# 10_Speaker_Microphone.net
KiCad netlist of a schematic drawn in Altium Designer
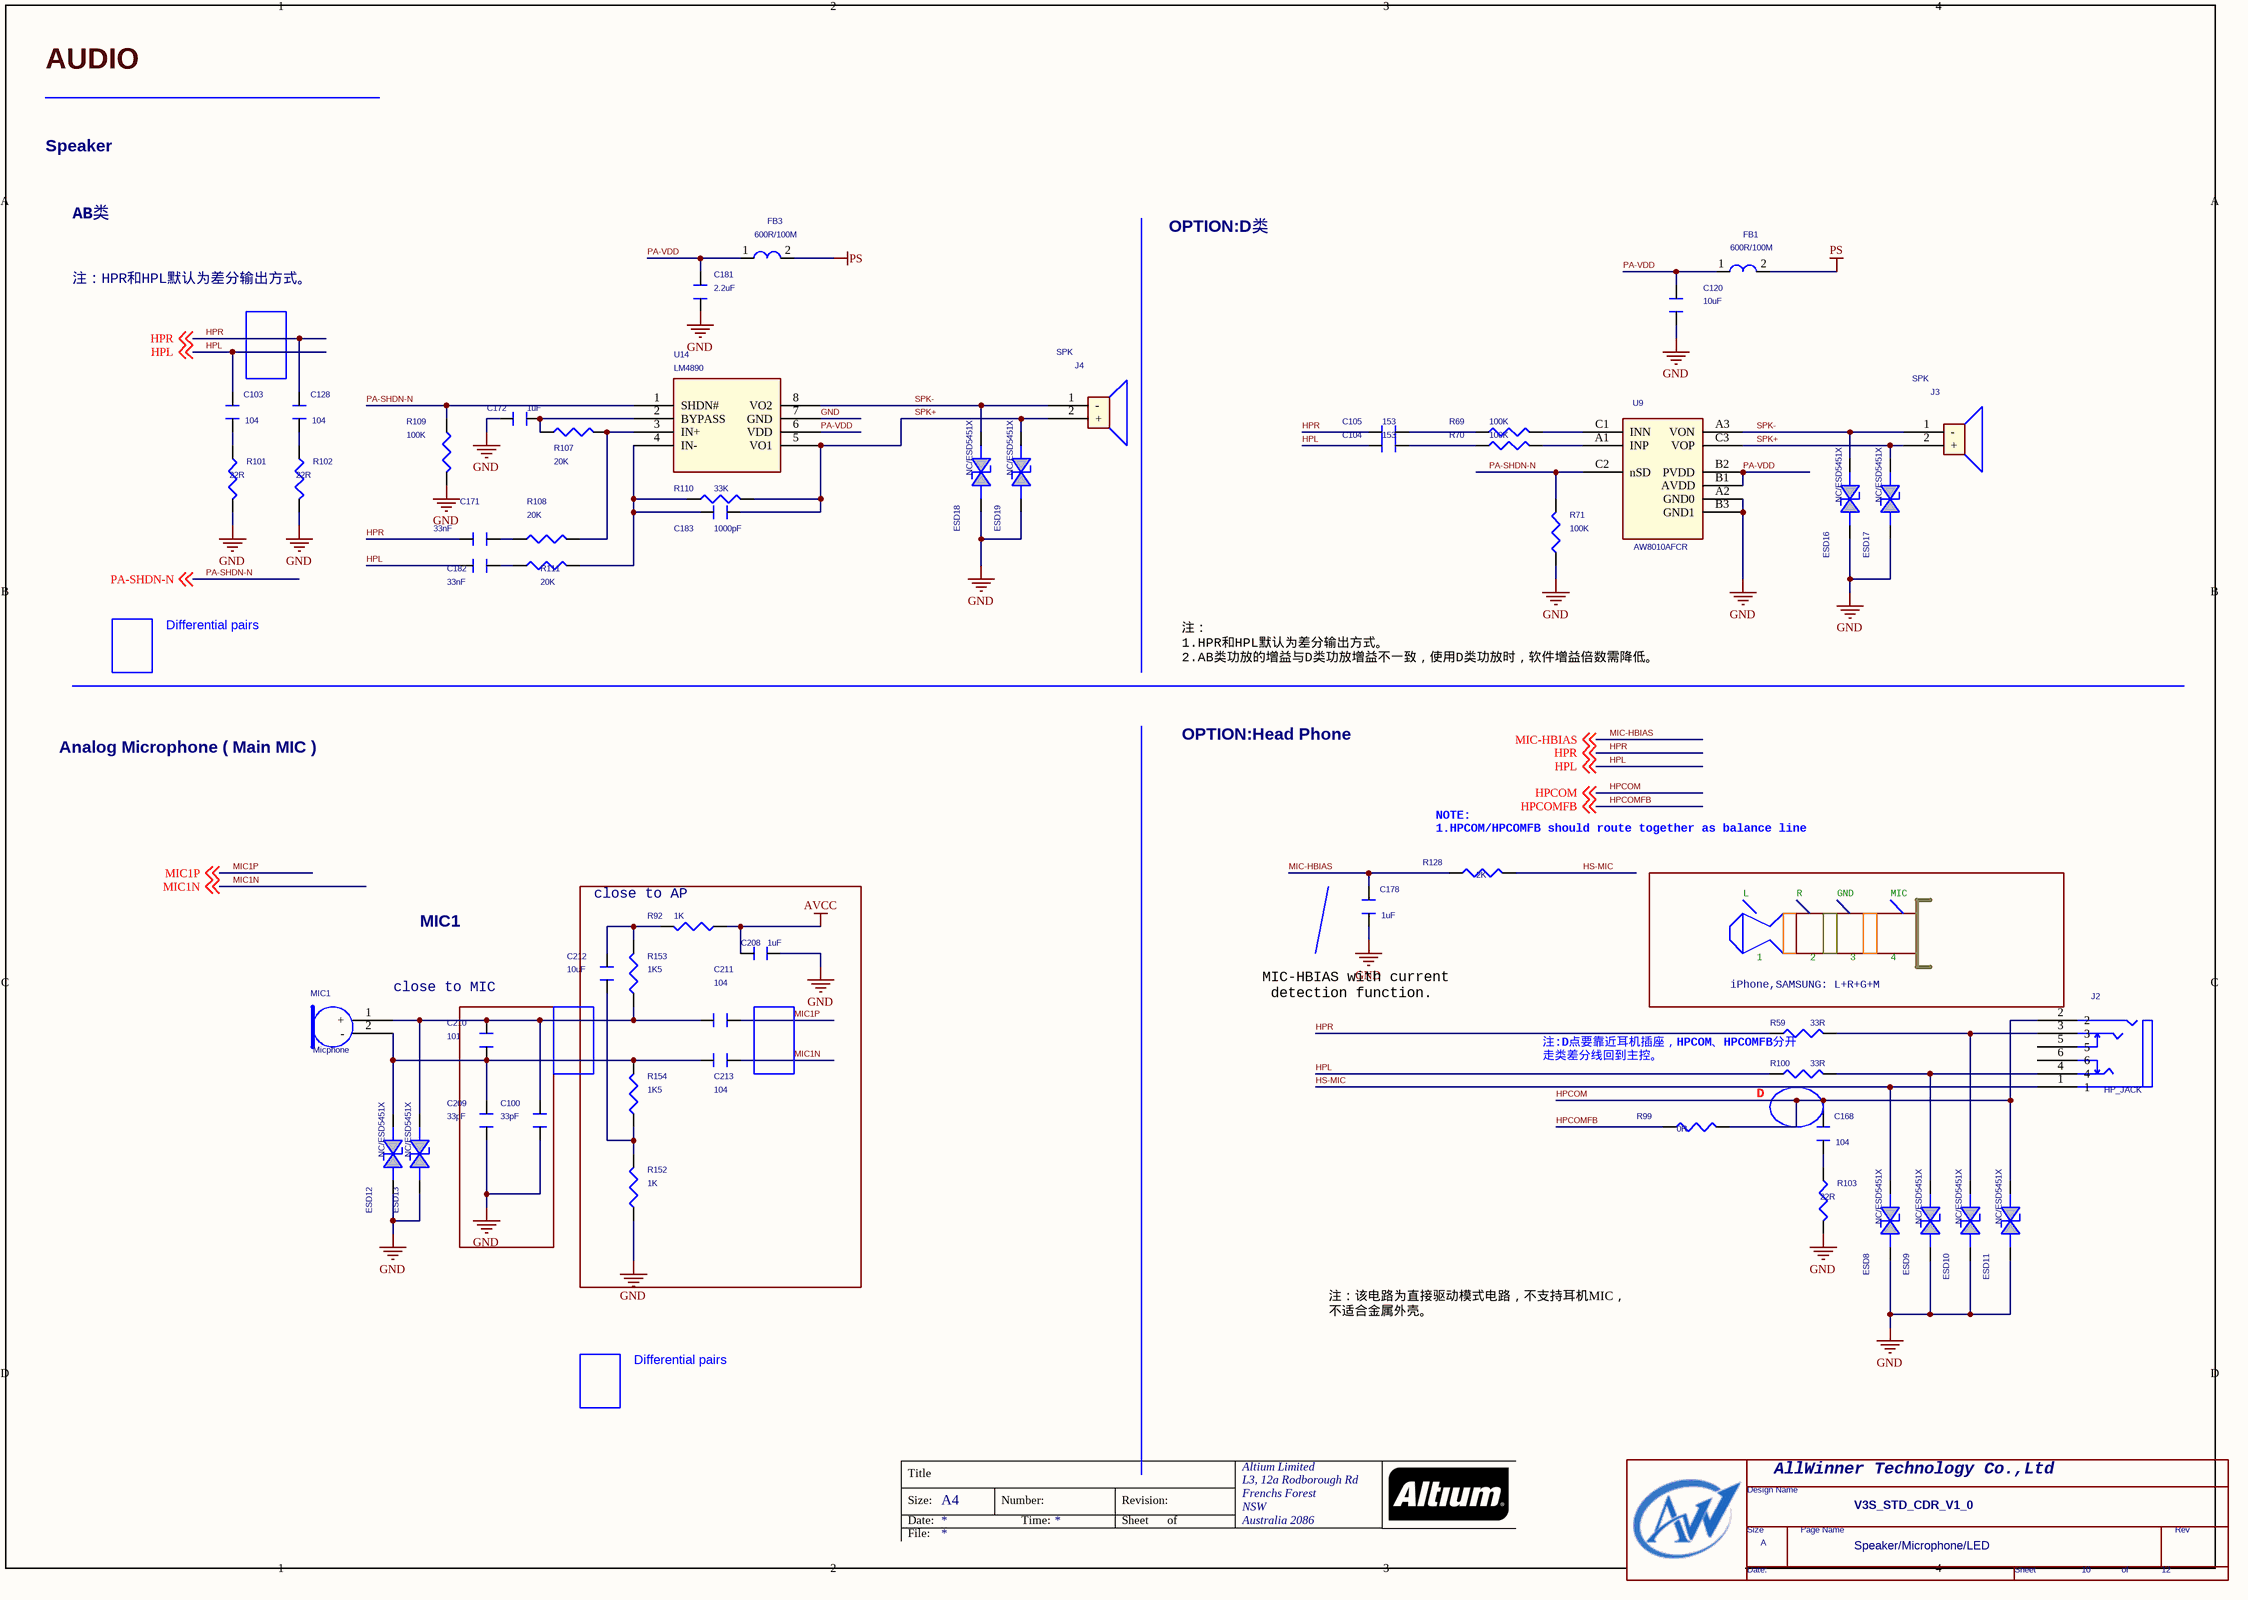
[diagram p0: 10 Speaker_Microphone.SchDoc]

(export (version "E")
  (design (tool "Eeschema 10.0.6"))
  (components
    (comp (ref "C100") (value "33pF") (footprint "C0402") (libsource (lib "*") (part "CAPACITOR")))
    (comp (ref "C103") (value "104") (footprint "C0402") (libsource (lib "*") (part "CAPACITOR_Dup1")))
    (comp (ref "C104") (value "153") (footprint "C0402") (libsource (lib "*") (part "CAPACITOR_0_Dup5")))
    (comp (ref "C105") (value "153") (footprint "C0402") (libsource (lib "*") (part "CAPACITOR_0_Dup5")))
    (comp (ref "C120") (value "10uF") (footprint "C0603") (libsource (lib "*") (part "CAPACITOR_Dup1")))
    (comp (ref "C128") (value "104") (footprint "C0402") (libsource (lib "*") (part "CAPACITOR_Dup1")))
    (comp (ref "C168") (value "104") (footprint "C0402") (libsource (lib "*") (part "CAPACITOR_Dup1")))
    (comp (ref "C171") (value "33nF") (footprint "C0402") (libsource (lib "*") (part "CAPACITOR_0_Dup3")))
    (comp (ref "C172") (value "1uF") (footprint "C0402") (libsource (lib "*") (part "CAPACITOR_0_Dup3")))
    (comp (ref "C178") (value "1uF") (footprint "C0402") (libsource (lib "*") (part "CAPACITOR_Dup1")))
    (comp (ref "C181") (value "2.2uF") (footprint "C0402") (libsource (lib "*") (part "CAPACITOR_0_Dup3")))
    (comp (ref "C182") (value "33nF") (footprint "C0402") (libsource (lib "*") (part "CAPACITOR_0_Dup3")))
    (comp (ref "C183") (value "1000pF") (footprint "C0402") (libsource (lib "*") (part "CAPACITOR_0_Dup3")))
    (comp (ref "C208") (value "1uF") (footprint "C0402") (libsource (lib "*") (part "CAPACITOR")))
    (comp (ref "C209") (value "33pF") (footprint "C0402") (libsource (lib "*") (part "CAPACITOR")))
    (comp (ref "C210") (value "101") (footprint "C0402") (libsource (lib "*") (part "CAPACITOR")))
    (comp (ref "C211") (value "104") (footprint "C0402") (libsource (lib "*") (part "CAPACITOR_Dup1")))
    (comp (ref "C212") (value "10uF") (footprint "C0603") (libsource (lib "*") (part "CAPACITOR_Dup1")))
    (comp (ref "C213") (value "104") (footprint "C0402") (libsource (lib "*") (part "CAPACITOR_Dup1")))
    (comp (ref "ESD8") (value "NC/ESD5451X") (footprint "ESD0402") (libsource (lib "*") (part "1_1.5KE100A")))
    (comp (ref "ESD9") (value "NC/ESD5451X") (footprint "ESD0402") (libsource (lib "*") (part "1_1.5KE100A")))
    (comp (ref "ESD10")
      (value "NC/ESD5451X")
      (footprint "ESD0402")
      (libsource (lib "*") (part "1_1.5KE100A"))
    )
    (comp (ref "ESD11")
      (value "NC/ESD5451X")
      (footprint "ESD0402")
      (libsource (lib "*") (part "1_1.5KE100A"))
    )
    (comp (ref "ESD12")
      (value "NC/ESD5451X")
      (footprint "ESD0402")
      (libsource (lib "*") (part "1_1.5KE100A"))
    )
    (comp (ref "ESD13")
      (value "NC/ESD5451X")
      (footprint "ESD0402")
      (libsource (lib "*") (part "1_1.5KE100A"))
    )
    (comp (ref "ESD16")
      (value "NC/ESD5451X")
      (footprint "ESD0402")
      (libsource (lib "*") (part "1_1.5KE100A"))
    )
    (comp (ref "ESD17")
      (value "NC/ESD5451X")
      (footprint "ESD0402")
      (libsource (lib "*") (part "1_1.5KE100A"))
    )
    (comp (ref "ESD18")
      (value "NC/ESD5451X")
      (footprint "ESD0402")
      (libsource (lib "*") (part "1_1.5KE100A"))
    )
    (comp (ref "ESD19")
      (value "NC/ESD5451X")
      (footprint "ESD0402")
      (libsource (lib "*") (part "1_1.5KE100A"))
    )
    (comp (ref "FB1")
      (value "600R/100M")
      (footprint "L0603")
      (description "RoHS BEAD/600ohm 100Mhz Z=600Ω DCR<0.2Ω 800mA SMT L0603")
      (libsource (lib "*") (part "INDUCTOR_0_Dup1"))
    )
    (comp (ref "FB3")
      (value "600R/100M")
      (footprint "L0603")
      (description "RoHS BEAD/600ohm 100Mhz Z=600Ω DCR<0.2Ω 800mA SMT L0603")
      (libsource (lib "*") (part "INDUCTOR_0_Dup1"))
    )
    (comp (ref "J2") (value "HP_JACK") (footprint "EAR-JACK-3-5") (libsource (lib "*") (part "USB_WIFI_0")))
    (comp (ref "J3") (value "SPK") (footprint "Phone Connector") (libsource (lib "*") (part "SPEAKER")))
    (comp (ref "J4") (value "SPK") (footprint "Phone Connector") (libsource (lib "*") (part "SPEAKER")))
    (comp (ref "MIC1")
      (value "Micphone")
      (footprint "Micphone Connector")
      (libsource (lib "*") (part "Micphone_0"))
    )
    (comp (ref "R59") (value "33R") (footprint "R0805") (libsource (lib "*") (part "R_Dup3")))
    (comp (ref "R69") (value "100K") (footprint "R0402") (libsource (lib "*") (part "RESISTOR_Dup2")))
    (comp (ref "R70") (value "100K") (footprint "R0402") (libsource (lib "*") (part "RESISTOR_Dup2")))
    (comp (ref "R71") (value "100K") (footprint "R0402") (libsource (lib "*") (part "R_Dup1")))
    (comp (ref "R92") (value "1K") (footprint "R0402") (libsource (lib "*") (part "R_Dup4")))
    (comp (ref "R99") (value "0R") (footprint "0805") (libsource (lib "*") (part "R1 0805_Dup1")))
    (comp (ref "R100") (value "33R") (footprint "R0805") (libsource (lib "*") (part "R_Dup3")))
    (comp (ref "R101") (value "22R") (footprint "0805") (libsource (lib "*") (part "R1 0805_Dup1")))
    (comp (ref "R102") (value "22R") (footprint "0805") (libsource (lib "*") (part "R1 0805_Dup1")))
    (comp (ref "R103") (value "22R") (footprint "0805") (libsource (lib "*") (part "R1 0805_Dup1")))
    (comp (ref "R107") (value "20K") (footprint "R0402") (libsource (lib "*") (part "?_0")))
    (comp (ref "R108") (value "20K") (footprint "R0402") (libsource (lib "*") (part "?_0")))
    (comp (ref "R109") (value "100K") (footprint "R0402") (libsource (lib "*") (part "?_0")))
    (comp (ref "R110") (value "33K") (footprint "R0402") (libsource (lib "*") (part "?_0")))
    (comp (ref "R111") (value "20K") (footprint "R0402") (libsource (lib "*") (part "?_0")))
    (comp (ref "R128") (value "2K") (footprint "R0402") (libsource (lib "*") (part "R_Dup4")))
    (comp (ref "R152") (value "1K") (footprint "R0402") (libsource (lib "*") (part "R_Dup4")))
    (comp (ref "R153") (value "1K5") (footprint "R0402") (libsource (lib "*") (part "R_Dup4")))
    (comp (ref "R154") (value "1K5") (footprint "R0402") (libsource (lib "*") (part "R_Dup4")))
    (comp (ref "U9") (value "AW8010AFCR") (footprint "CSP9") (libsource (lib "*") (part "AW8010CSR_1")))
    (comp (ref "U14") (value "LM4890") (footprint "MSOP8") (libsource (lib "*") (part "LY8006_0")))
  )
  (nets
    (net (code "1") (name "/HS-MIC") (class "Default")
      (node (ref "ESD8") (pin "1") (pinfunction "ANODE_1") (pintype "passive"))
      (node (ref "J2") (pin "1") (pinfunction "1_1") (pintype "passive"))
      (node (ref "R128") (pin "1") (pinfunction "1_1") (pintype "passive"))
    )
    (net (code "2") (name "/PA-VDD") (class "Default")
      (node (ref "C120") (pin "2") (pinfunction "2_2") (pintype "passive"))
      (node (ref "C181") (pin "2") (pinfunction "2_2") (pintype "passive"))
      (node (ref "FB1") (pin "1") (pinfunction "1_1") (pintype "passive"))
      (node (ref "FB3") (pin "1") (pinfunction "1_1") (pintype "passive"))
      (node (ref "U14") (pin "6") (pinfunction "VDD_6") (pintype "passive"))
      (node (ref "U9") (pin "B1") (pinfunction "AVDD_B1") (pintype "passive"))
      (node (ref "U9") (pin "B2") (pinfunction "PVDD_B2") (pintype "passive"))
    )
    (net (code "3") (name "/SPK+") (class "Default")
      (node (ref "C183") (pin "2") (pinfunction "2_2") (pintype "passive"))
      (node (ref "ESD17") (pin "1") (pinfunction "ANODE_1") (pintype "passive"))
      (node (ref "ESD19") (pin "1") (pinfunction "ANODE_1") (pintype "passive"))
      (node (ref "J3") (pin "2") (pinfunction "+_2") (pintype "passive"))
      (node (ref "J4") (pin "2") (pinfunction "+_2") (pintype "passive"))
      (node (ref "R110") (pin "2") (pinfunction "2_2") (pintype "passive"))
      (node (ref "U14") (pin "5") (pinfunction "VO1_5") (pintype "passive"))
      (node (ref "U9") (pin "C3") (pinfunction "VOP_C3") (pintype "passive"))
    )
    (net (code "4") (name "/SPK-") (class "Default")
      (node (ref "ESD16") (pin "1") (pinfunction "ANODE_1") (pintype "passive"))
      (node (ref "ESD18") (pin "1") (pinfunction "ANODE_1") (pintype "passive"))
      (node (ref "J3") (pin "1") (pinfunction "-_1") (pintype "passive"))
      (node (ref "J4") (pin "1") (pinfunction "-_1") (pintype "passive"))
      (node (ref "U14") (pin "8") (pinfunction "VO2_8") (pintype "passive"))
      (node (ref "U9") (pin "A3") (pinfunction "VON_A3") (pintype "passive"))
    )
    (net (code "5") (name "AVCC") (class "Default")
      (node (ref "C208") (pin "2") (pinfunction "2_2") (pintype "passive"))
      (node (ref "R92") (pin "1") (pinfunction "1_1") (pintype "passive"))
    )
    (net (code "6") (name "GND") (class "Default")
      (node (ref "C100") (pin "1") (pinfunction "1_1") (pintype "passive"))
      (node (ref "C120") (pin "1") (pinfunction "1_1") (pintype "passive"))
      (node (ref "C172") (pin "1") (pinfunction "1_1") (pintype "passive"))
      (node (ref "C178") (pin "1") (pinfunction "1_1") (pintype "passive"))
      (node (ref "C181") (pin "1") (pinfunction "1_1") (pintype "passive"))
      (node (ref "C208") (pin "1") (pinfunction "1_1") (pintype "passive"))
      (node (ref "C209") (pin "1") (pinfunction "1_1") (pintype "passive"))
      (node (ref "ESD10") (pin "2") (pinfunction "CATHODE_2") (pintype "passive"))
      (node (ref "ESD11") (pin "2") (pinfunction "CATHODE_2") (pintype "passive"))
      (node (ref "ESD12") (pin "2") (pinfunction "CATHODE_2") (pintype "passive"))
      (node (ref "ESD13") (pin "2") (pinfunction "CATHODE_2") (pintype "passive"))
      (node (ref "ESD16") (pin "2") (pinfunction "CATHODE_2") (pintype "passive"))
      (node (ref "ESD17") (pin "2") (pinfunction "CATHODE_2") (pintype "passive"))
      (node (ref "ESD18") (pin "2") (pinfunction "CATHODE_2") (pintype "passive"))
      (node (ref "ESD19") (pin "2") (pinfunction "CATHODE_2") (pintype "passive"))
      (node (ref "ESD8") (pin "2") (pinfunction "CATHODE_2") (pintype "passive"))
      (node (ref "ESD9") (pin "2") (pinfunction "CATHODE_2") (pintype "passive"))
      (node (ref "R101") (pin "1") (pinfunction "1_1") (pintype "passive"))
      (node (ref "R102") (pin "1") (pinfunction "1_1") (pintype "passive"))
      (node (ref "R103") (pin "1") (pinfunction "1_1") (pintype "passive"))
      (node (ref "R109") (pin "2") (pinfunction "2_2") (pintype "passive"))
      (node (ref "R152") (pin "1") (pinfunction "1_1") (pintype "passive"))
      (node (ref "R71") (pin "1") (pinfunction "1_1") (pintype "passive"))
      (node (ref "U14") (pin "7") (pinfunction "GND_7") (pintype "passive"))
      (node (ref "U9") (pin "A2") (pinfunction "GND0_A2") (pintype "passive"))
      (node (ref "U9") (pin "B3") (pinfunction "GND1_B3") (pintype "passive"))
    )
    (net (code "7") (name "HPCOM") (class "Default")
      (node (ref "C168") (pin "2") (pinfunction "2_2") (pintype "passive"))
      (node (ref "ESD11") (pin "1") (pinfunction "ANODE_1") (pintype "passive"))
      (node (ref "J2") (pin "2") (pinfunction "2_2") (pintype "passive"))
      (node (ref "R99") (pin "1") (pinfunction "1_1") (pintype "passive"))
    )
    (net (code "8") (name "HPCOMFB") (class "Default")
      (node (ref "R99") (pin "2") (pinfunction "2_2") (pintype "passive"))
    )
    (net (code "9") (name "HPL") (class "Default")
      (node (ref "C103") (pin "2") (pinfunction "2_2") (pintype "passive"))
      (node (ref "C104") (pin "2") (pinfunction "2_2") (pintype "passive"))
      (node (ref "C182") (pin "1") (pinfunction "1_1") (pintype "passive"))
      (node (ref "R100") (pin "1") (pinfunction "1_1") (pintype "passive"))
    )
    (net (code "10") (name "HPR") (class "Default")
      (node (ref "C105") (pin "2") (pinfunction "2_2") (pintype "passive"))
      (node (ref "C128") (pin "2") (pinfunction "2_2") (pintype "passive"))
      (node (ref "C171") (pin "1") (pinfunction "1_1") (pintype "passive"))
      (node (ref "R59") (pin "1") (pinfunction "1_1") (pintype "passive"))
    )
    (net (code "11") (name "MIC-HBIAS") (class "Default")
      (node (ref "C178") (pin "2") (pinfunction "2_2") (pintype "passive"))
      (node (ref "R128") (pin "2") (pinfunction "2_2") (pintype "passive"))
    )
    (net (code "12") (name "MIC1N") (class "Default")
      (node (ref "C213") (pin "1") (pinfunction "1_1") (pintype "passive"))
    )
    (net (code "13") (name "MIC1P") (class "Default")
      (node (ref "C211") (pin "1") (pinfunction "1_1") (pintype "passive"))
    )
    (net (code "14") (name "Net-(C103-Pad1)") (class "Default")
      (node (ref "C103") (pin "1") (pinfunction "1_1") (pintype "passive"))
      (node (ref "R101") (pin "2") (pinfunction "2_2") (pintype "passive"))
    )
    (net (code "15") (name "Net-(C104-Pad1)") (class "Default")
      (node (ref "C104") (pin "1") (pinfunction "1_1") (pintype "passive"))
      (node (ref "R70") (pin "1") (pinfunction "1_1") (pintype "passive"))
    )
    (net (code "16") (name "Net-(C105-Pad1)") (class "Default")
      (node (ref "C105") (pin "1") (pinfunction "1_1") (pintype "passive"))
      (node (ref "R69") (pin "1") (pinfunction "1_1") (pintype "passive"))
    )
    (net (code "17") (name "Net-(C128-Pad1)") (class "Default")
      (node (ref "C128") (pin "1") (pinfunction "1_1") (pintype "passive"))
      (node (ref "R102") (pin "2") (pinfunction "2_2") (pintype "passive"))
    )
    (net (code "18") (name "Net-(C168-Pad1)") (class "Default")
      (node (ref "C168") (pin "1") (pinfunction "1_1") (pintype "passive"))
      (node (ref "R103") (pin "2") (pinfunction "2_2") (pintype "passive"))
    )
    (net (code "19") (name "Net-(C171-Pad2)") (class "Default")
      (node (ref "C171") (pin "2") (pinfunction "2_2") (pintype "passive"))
      (node (ref "R108") (pin "1") (pinfunction "1_1") (pintype "passive"))
    )
    (net (code "20") (name "Net-(C182-Pad2)") (class "Default")
      (node (ref "C182") (pin "2") (pinfunction "2_2") (pintype "passive"))
      (node (ref "R111") (pin "1") (pinfunction "1_1") (pintype "passive"))
    )
    (net (code "21") (name "Net-(C212-Pad1)") (class "Default")
      (node (ref "C212") (pin "1") (pinfunction "1_1") (pintype "passive"))
      (node (ref "R152") (pin "2") (pinfunction "2_2") (pintype "passive"))
      (node (ref "R154") (pin "1") (pinfunction "1_1") (pintype "passive"))
    )
    (net (code "22") (name "Net-(C212-Pad2)") (class "Default")
      (node (ref "C212") (pin "2") (pinfunction "2_2") (pintype "passive"))
      (node (ref "R153") (pin "2") (pinfunction "2_2") (pintype "passive"))
      (node (ref "R92") (pin "2") (pinfunction "2_2") (pintype "passive"))
    )
    (net (code "23") (name "Net-(ESD9-ANODE)") (class "Default")
      (node (ref "ESD9") (pin "1") (pinfunction "ANODE_1") (pintype "passive"))
      (node (ref "J2") (pin "4") (pinfunction "4_4") (pintype "passive"))
      (node (ref "R100") (pin "2") (pinfunction "2_2") (pintype "passive"))
    )
    (net (code "24") (name "Net-(ESD10-ANODE)") (class "Default")
      (node (ref "ESD10") (pin "1") (pinfunction "ANODE_1") (pintype "passive"))
      (node (ref "J2") (pin "3") (pinfunction "3_3") (pintype "passive"))
      (node (ref "R59") (pin "2") (pinfunction "2_2") (pintype "passive"))
    )
    (net (code "25") (name "Net-(ESD12-ANODE)") (class "Default")
      (node (ref "C209") (pin "2") (pinfunction "2_2") (pintype "passive"))
      (node (ref "C210") (pin "1") (pinfunction "1_1") (pintype "passive"))
      (node (ref "C213") (pin "2") (pinfunction "2_2") (pintype "passive"))
      (node (ref "ESD12") (pin "1") (pinfunction "ANODE_1") (pintype "passive"))
      (node (ref "MIC1") (pin "2") (pinfunction "-_2") (pintype "passive"))
      (node (ref "R154") (pin "2") (pinfunction "2_2") (pintype "passive"))
    )
    (net (code "26") (name "Net-(ESD13-ANODE)") (class "Default")
      (node (ref "C100") (pin "2") (pinfunction "2_2") (pintype "passive"))
      (node (ref "C210") (pin "2") (pinfunction "2_2") (pintype "passive"))
      (node (ref "C211") (pin "2") (pinfunction "2_2") (pintype "passive"))
      (node (ref "ESD13") (pin "1") (pinfunction "ANODE_1") (pintype "passive"))
      (node (ref "MIC1") (pin "1") (pinfunction "+_1") (pintype "passive"))
      (node (ref "R153") (pin "1") (pinfunction "1_1") (pintype "passive"))
    )
    (net (code "27") (name "Net-(U9-INN)") (class "Default")
      (node (ref "R69") (pin "2") (pinfunction "2_2") (pintype "passive"))
      (node (ref "U9") (pin "C1") (pinfunction "INN_C1") (pintype "passive"))
    )
    (net (code "28") (name "Net-(U9-INP)") (class "Default")
      (node (ref "R70") (pin "2") (pinfunction "2_2") (pintype "passive"))
      (node (ref "U9") (pin "A1") (pinfunction "INP_A1") (pintype "passive"))
    )
    (net (code "29") (name "Net-(U14-BYPASS)") (class "Default")
      (node (ref "C172") (pin "2") (pinfunction "2_2") (pintype "passive"))
      (node (ref "R107") (pin "1") (pinfunction "1_1") (pintype "passive"))
      (node (ref "U14") (pin "2") (pinfunction "BYPASS_2") (pintype "passive"))
    )
    (net (code "30") (name "Net-(U14-IN+)") (class "Default")
      (node (ref "R107") (pin "2") (pinfunction "2_2") (pintype "passive"))
      (node (ref "R108") (pin "2") (pinfunction "2_2") (pintype "passive"))
      (node (ref "U14") (pin "3") (pinfunction "IN+_3") (pintype "passive"))
    )
    (net (code "31") (name "Net-(U14-IN-)") (class "Default")
      (node (ref "C183") (pin "1") (pinfunction "1_1") (pintype "passive"))
      (node (ref "R110") (pin "1") (pinfunction "1_1") (pintype "passive"))
      (node (ref "R111") (pin "2") (pinfunction "2_2") (pintype "passive"))
      (node (ref "U14") (pin "4") (pinfunction "IN-_4") (pintype "passive"))
    )
    (net (code "32") (name "PA-SHDN-N") (class "Default")
      (node (ref "R109") (pin "1") (pinfunction "1_1") (pintype "passive"))
      (node (ref "R71") (pin "2") (pinfunction "2_2") (pintype "passive"))
      (node (ref "U14") (pin "1") (pinfunction "SHDN#_1") (pintype "passive"))
      (node (ref "U9") (pin "C2") (pinfunction "nSD_C2") (pintype "passive"))
    )
    (net (code "33") (name "PS") (class "Default")
      (node (ref "FB1") (pin "2") (pinfunction "2_2") (pintype "passive"))
      (node (ref "FB3") (pin "2") (pinfunction "2_2") (pintype "passive"))
    )
    (net (code "34") (name "unconnected-(J2-Pad5)") (class "Default")
      (node (ref "J2") (pin "5") (pinfunction "5_5") (pintype "passive"))
    )
    (net (code "35") (name "unconnected-(J2-Pad6)") (class "Default")
      (node (ref "J2") (pin "6") (pinfunction "6_6") (pintype "passive"))
    )
  )
)
